# Opto_v2.net
KiCad netlist of a schematic drawn in EAGLE
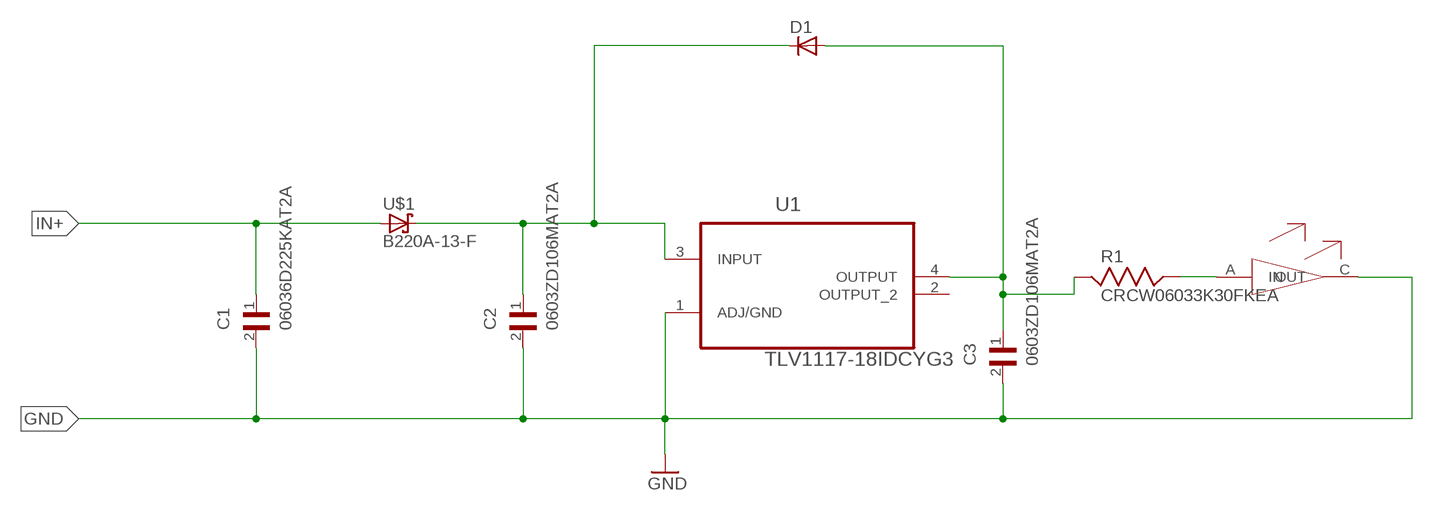
[diagram p0: schematic, sheet 1]

(export (version "E")
  (design (tool "Eeschema 10.0.6"))
  (components
    (comp (ref "C1")
      (value "06036D225KAT2A")
      (footprint "eagle-import:CAPC1608X90")
      (fields (field (name "DIGI-KEY_PART_NUMBER") "478-1252-1-ND") (field (name "MF") "AVX"))
      (libsource (lib "eagle-import") (part "06036D225KAT2A"))
    )
    (comp (ref "C2")
      (value "0603ZD106MAT2A")
      (footprint "eagle-import:CAPC1608X90")
      (fields (field (name "DIGI-KEY_PART_NUMBER") "478-8050-1-ND") (field (name "MF") "AVX"))
      (libsource (lib "eagle-import") (part "0603ZD106MAT2A"))
    )
    (comp (ref "C3")
      (value "0603ZD106MAT2A")
      (footprint "eagle-import:CAPC1608X90")
      (fields (field (name "DIGI-KEY_PART_NUMBER") "478-8050-1-ND") (field (name "MF") "AVX"))
      (libsource (lib "eagle-import") (part "0603ZD106MAT2A"))
    )
    (comp (ref "D1")
      (value "BYS10")
      (footprint "eagle-import:SOD106A")
      (fields (field (name "MPN") "BYS10/45"))
      (libsource (lib "eagle-import") (part "BYS10"))
    )
    (comp (ref "R1")
      (value "CRCW06033K30FKEA")
      (footprint "eagle-import:RESC1608X55")
      (fields (field (name "DIGI-KEY_PART_NUMBER") "541-3.30KHCT-ND") (field (name "MF") "Vishay Dale"))
      (libsource (lib "eagle-import") (part "CRCW06033K30FKEA"))
    )
    (comp (ref "U$1")
      (value "B220A-13-F")
      (footprint "eagle-import:SMA-DIODE")
      (fields (field (name "DIGI-KEY_PART_NUMBER") "B220A-FDICT-ND") (field (name "MF") "Diodes Inc."))
      (libsource (lib "eagle-import") (part "B220A-13-F"))
    )
    (comp (ref "U$3")
      (value "LED")
      (footprint "eagle-import:LEDM1608X80")
      (libsource (lib "eagle-import") (part "LED"))
    )
    (comp (ref "U1")
      (value "TLV1117-18IDCYG3")
      (footprint "eagle-import:SOT230P700X180-4N")
      (fields (field (name "MF") "Texas Instruments"))
      (libsource (lib "eagle-import") (part "TLV1117-18IDCYG3"))
    )
  )
  (nets
    (net (code "1") (name "GND") (class "Default")
      (node (ref "C1") (pin "2") (pinfunction "2_2") (pintype "passive"))
      (node (ref "C2") (pin "2") (pinfunction "2_2") (pintype "passive"))
      (node (ref "C3") (pin "2") (pinfunction "2_2") (pintype "passive"))
      (node (ref "U$3") (pin "C") (pinfunction "OUT_C") (pintype "bidirectional"))
      (node (ref "U1") (pin "1") (pinfunction "ADJ/GND_1") (pintype "input"))
    )
    (net (code "2") (name "IN+") (class "Default")
      (node (ref "C1") (pin "1") (pinfunction "1_1") (pintype "passive"))
      (node (ref "U$1") (pin "1") (pinfunction "A_1") (pintype "passive"))
    )
    (net (code "3") (name "Net-(U$1-C)") (class "Default")
      (node (ref "C2") (pin "1") (pinfunction "1_1") (pintype "passive"))
      (node (ref "D1") (pin "K") (pinfunction "K_K") (pintype "passive"))
      (node (ref "U$1") (pin "2") (pinfunction "C_2") (pintype "passive"))
      (node (ref "U1") (pin "3") (pinfunction "INPUT_3") (pintype "input"))
    )
    (net (code "4") (name "Net-(U$3-IN)") (class "Default")
      (node (ref "R1") (pin "2") (pinfunction "2_2") (pintype "passive"))
      (node (ref "U$3") (pin "A") (pinfunction "IN_A") (pintype "bidirectional"))
    )
    (net (code "5") (name "Net-(U1-OUTPUT)") (class "Default")
      (node (ref "C3") (pin "1") (pinfunction "1_1") (pintype "passive"))
      (node (ref "D1") (pin "A") (pinfunction "A_A") (pintype "passive"))
      (node (ref "R1") (pin "1") (pinfunction "1_1") (pintype "passive"))
      (node (ref "U1") (pin "4") (pinfunction "OUTPUT_4") (pintype "output"))
    )
    (net (code "6") (name "unconnected-(U1-OUTPUT_2-Pad2)") (class "Default")
      (node (ref "U1") (pin "2") (pinfunction "OUTPUT_2_2") (pintype "output"))
    )
  )
)
